# SOIC8.net
KiCad netlist of a schematic drawn in EAGLE
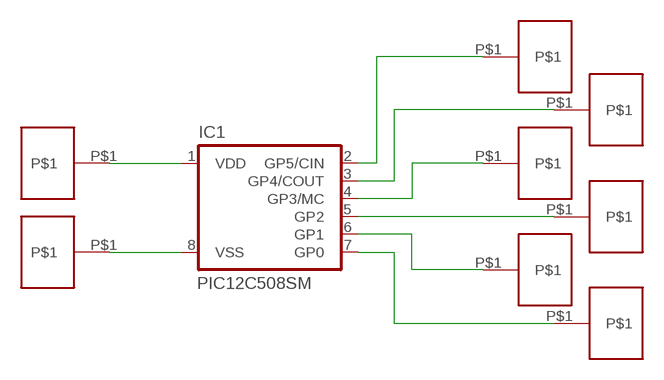
[diagram p0: schematic, sheet 1]

(export (version "E")
  (design (tool "Eeschema 10.0.6"))
  (components
    (comp (ref "IC1")
      (value "PIC12C508SM")
      (footprint "eagle-import:SO-08M")
      (fields (field (name "MF") "MICROCHIP") (field (name "MPN") "PIC12C508-04I/SM"))
      (libsource (lib "eagle-import") (part "PIC12C?SM508"))
    )
    (comp (ref "U$1")
      (value "PAD50X100MIL")
      (footprint "eagle-import:100X50MIL_PAD")
      (libsource (lib "eagle-import") (part "PAD50X100MIL"))
    )
    (comp (ref "U$2")
      (value "PAD50X100MIL")
      (footprint "eagle-import:100X50MIL_PAD")
      (libsource (lib "eagle-import") (part "PAD50X100MIL"))
    )
    (comp (ref "U$3")
      (value "PAD50X100MIL")
      (footprint "eagle-import:100X50MIL_PAD")
      (libsource (lib "eagle-import") (part "PAD50X100MIL"))
    )
    (comp (ref "U$4")
      (value "PAD50X100MIL")
      (footprint "eagle-import:100X50MIL_PAD")
      (libsource (lib "eagle-import") (part "PAD50X100MIL"))
    )
    (comp (ref "U$5")
      (value "PAD50X100MIL")
      (footprint "eagle-import:100X50MIL_PAD")
      (libsource (lib "eagle-import") (part "PAD50X100MIL"))
    )
    (comp (ref "U$6")
      (value "PAD50X100MIL")
      (footprint "eagle-import:100X50MIL_PAD")
      (libsource (lib "eagle-import") (part "PAD50X100MIL"))
    )
    (comp (ref "U$7")
      (value "PAD50X100MIL")
      (footprint "eagle-import:100X50MIL_PAD")
      (libsource (lib "eagle-import") (part "PAD50X100MIL"))
    )
    (comp (ref "U$8")
      (value "PAD50X100MIL")
      (footprint "eagle-import:100X50MIL_PAD")
      (libsource (lib "eagle-import") (part "PAD50X100MIL"))
    )
  )
  (nets
    (net (code "1") (name "Net-(IC1-GP0)") (class "Default")
      (node (ref "IC1") (pin "7") (pinfunction "GP0_7") (pintype "bidirectional"))
      (node (ref "U$7") (pin "P$1") (pinfunction "P$1_P$1") (pintype "bidirectional"))
    )
    (net (code "2") (name "Net-(IC1-GP1)") (class "Default")
      (node (ref "IC1") (pin "6") (pinfunction "GP1_6") (pintype "bidirectional"))
      (node (ref "U$4") (pin "P$1") (pinfunction "P$1_P$1") (pintype "bidirectional"))
    )
    (net (code "3") (name "Net-(IC1-GP2)") (class "Default")
      (node (ref "IC1") (pin "5") (pinfunction "GP2_5") (pintype "bidirectional"))
      (node (ref "U$5") (pin "P$1") (pinfunction "P$1_P$1") (pintype "bidirectional"))
    )
    (net (code "4") (name "Net-(IC1-GP3{slash}MC)") (class "Default")
      (node (ref "IC1") (pin "4") (pinfunction "GP3/MC_4") (pintype "input"))
      (node (ref "U$3") (pin "P$1") (pinfunction "P$1_P$1") (pintype "bidirectional"))
    )
    (net (code "5") (name "Net-(IC1-GP4{slash}COUT)") (class "Default")
      (node (ref "IC1") (pin "3") (pinfunction "GP4/COUT_3") (pintype "bidirectional"))
      (node (ref "U$6") (pin "P$1") (pinfunction "P$1_P$1") (pintype "bidirectional"))
    )
    (net (code "6") (name "Net-(IC1-GP5{slash}CIN)") (class "Default")
      (node (ref "IC1") (pin "2") (pinfunction "GP5/CIN_2") (pintype "bidirectional"))
      (node (ref "U$8") (pin "P$1") (pinfunction "P$1_P$1") (pintype "bidirectional"))
    )
    (net (code "7") (name "Net-(IC1-VDD)") (class "Default")
      (node (ref "IC1") (pin "1") (pinfunction "VDD_1") (pintype "power_in"))
      (node (ref "U$1") (pin "P$1") (pinfunction "P$1_P$1") (pintype "bidirectional"))
    )
    (net (code "8") (name "Net-(IC1-VSS)") (class "Default")
      (node (ref "IC1") (pin "8") (pinfunction "VSS_8") (pintype "power_in"))
      (node (ref "U$2") (pin "P$1") (pinfunction "P$1_P$1") (pintype "bidirectional"))
    )
  )
)
